# Sonar-Amplifier.net
KiCad netlist of a schematic drawn in EAGLE
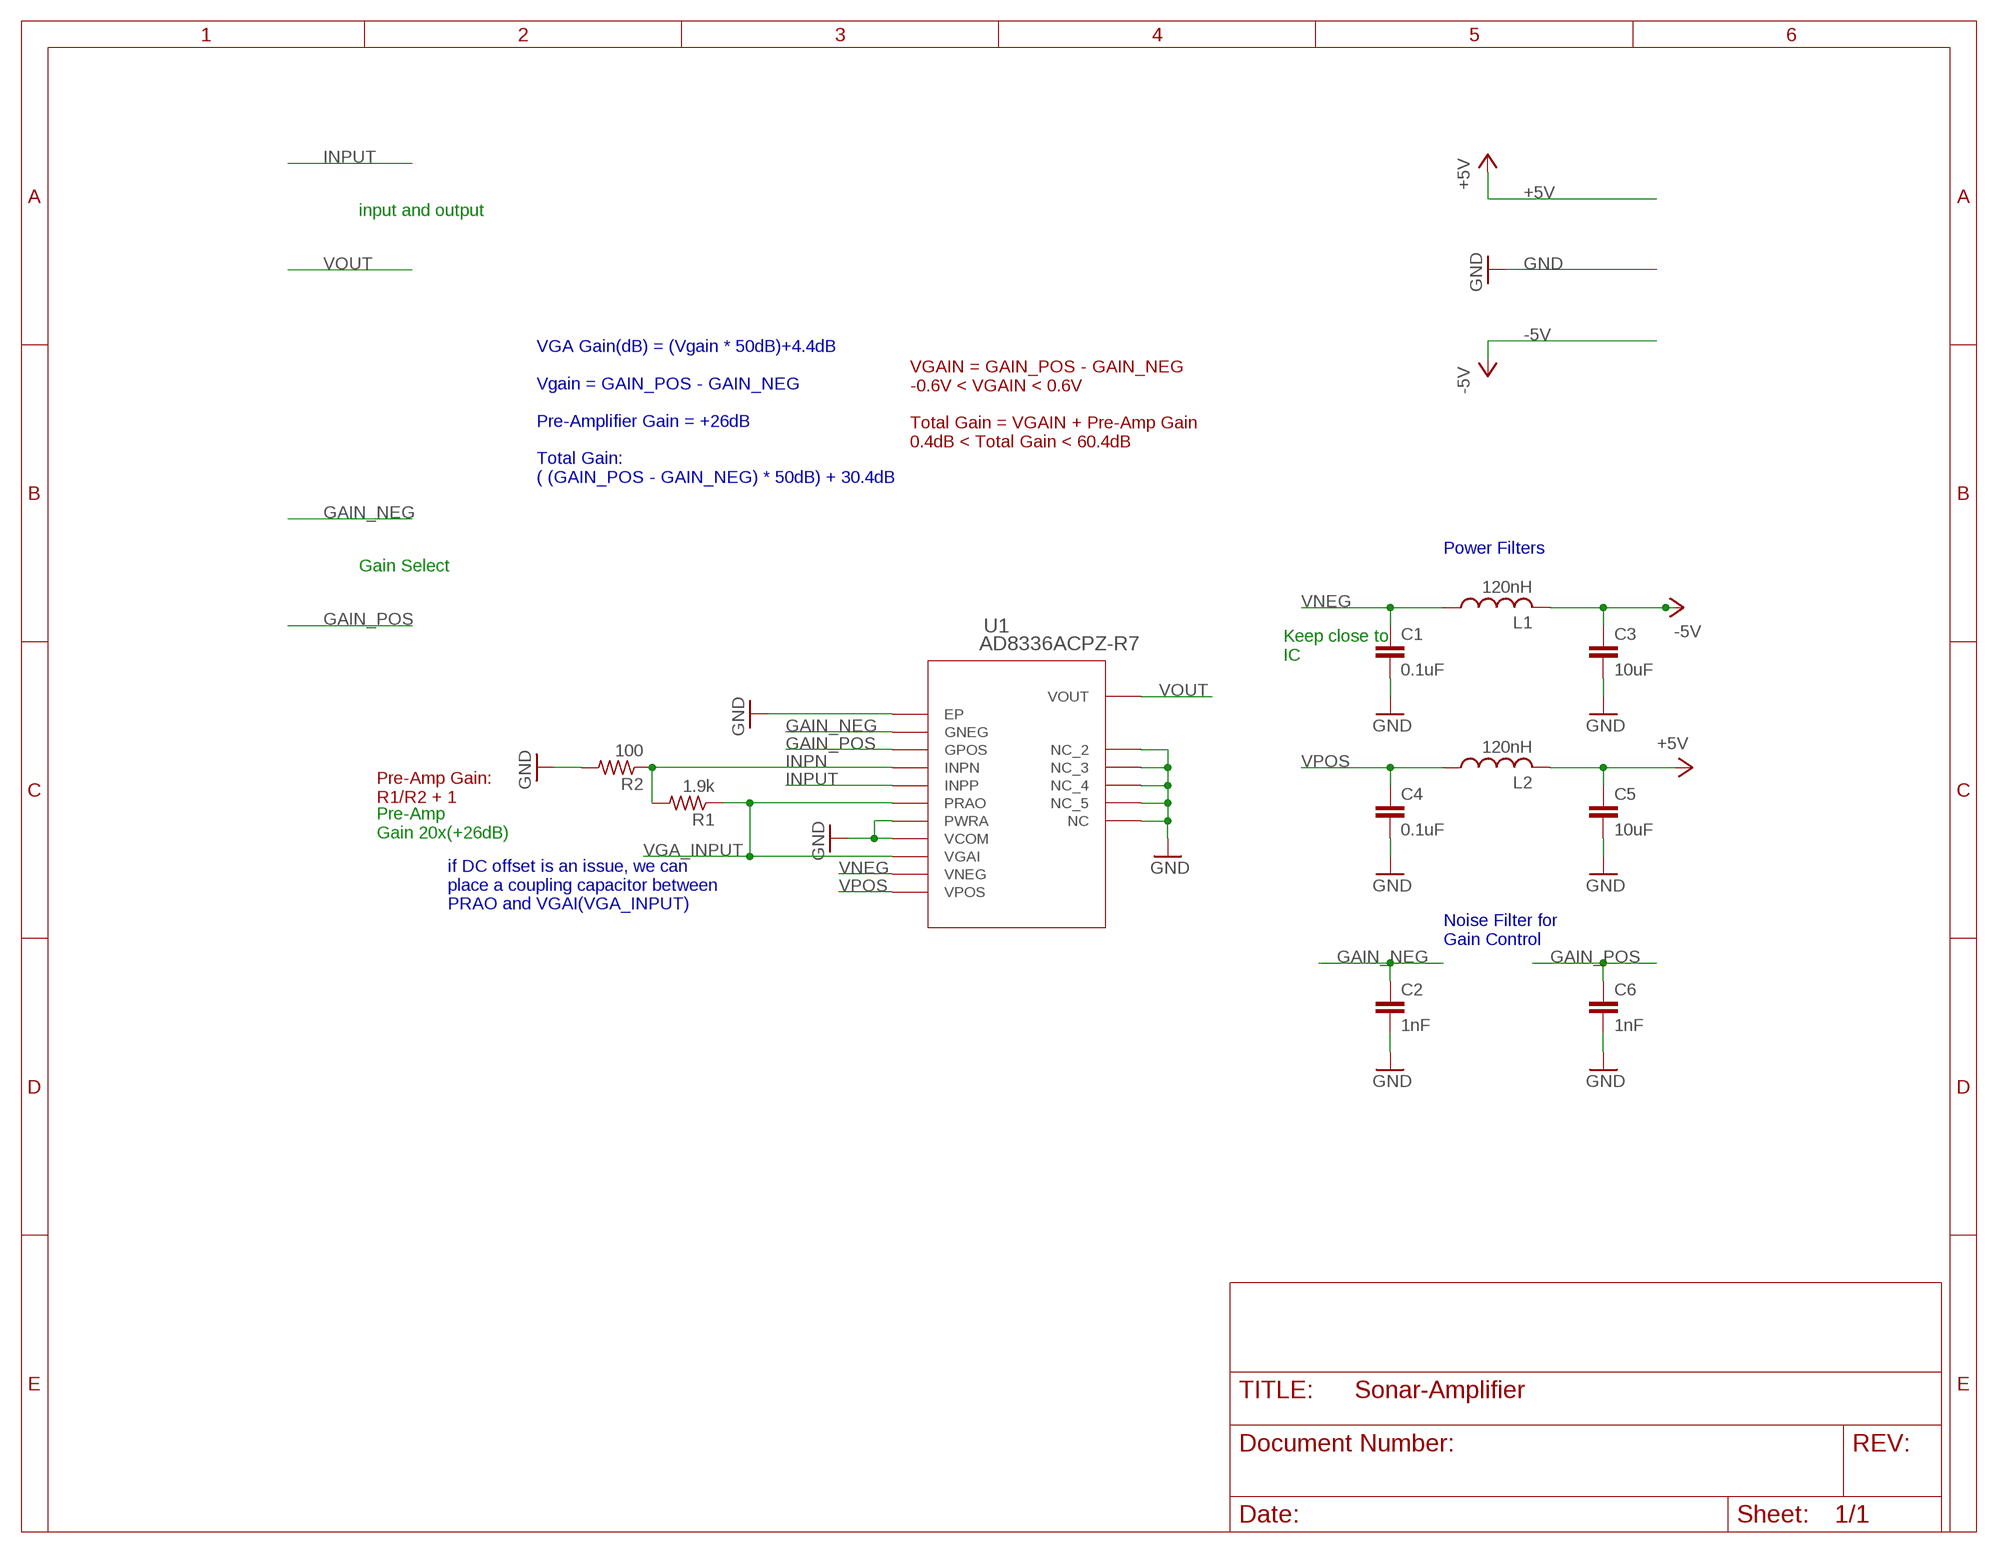
[diagram p0: schematic, sheet 1]

(export (version "E")
  (design (tool "Eeschema 10.0.6"))
  (components
    (comp (ref "C1")
      (value "0.1uF")
      (footprint "eagle-import:C0603")
      (libsource (lib "eagle-import") (part "C-EUC0603"))
    )
    (comp (ref "C2")
      (value "1nF")
      (footprint "eagle-import:C0603")
      (libsource (lib "eagle-import") (part "C-EUC0603"))
    )
    (comp (ref "C3")
      (value "10uF")
      (footprint "eagle-import:C1206")
      (libsource (lib "eagle-import") (part "resistor_348_C-EUC1206"))
    )
    (comp (ref "C4")
      (value "0.1uF")
      (footprint "eagle-import:C0603")
      (libsource (lib "eagle-import") (part "C-EUC0603"))
    )
    (comp (ref "C5")
      (value "10uF")
      (footprint "eagle-import:C1206")
      (libsource (lib "eagle-import") (part "resistor_348_C-EUC1206"))
    )
    (comp (ref "C6")
      (value "1nF")
      (footprint "eagle-import:C0603")
      (libsource (lib "eagle-import") (part "C-EUC0603"))
    )
    (comp (ref "L1")
      (value "120nH")
      (footprint "eagle-import:L3225P")
      (libsource (lib "eagle-import") (part "L-USL3225P"))
    )
    (comp (ref "L2")
      (value "120nH")
      (footprint "eagle-import:L3225P")
      (libsource (lib "eagle-import") (part "L-USL3225P"))
    )
    (comp (ref "R1")
      (value "1.9k")
      (footprint "eagle-import:R0603")
      (libsource (lib "eagle-import") (part "R-US_R0603"))
    )
    (comp (ref "R2")
      (value "100")
      (footprint "eagle-import:R0603")
      (libsource (lib "eagle-import") (part "R-US_R0603"))
    )
    (comp (ref "U1")
      (value "AD8336ACPZ-R7")
      (footprint "eagle-import:CP_16_4")
      (fields (field (name "MANUFACTURER_PART_NUMBER") "AD8336ACPZR7"))
      (libsource (lib "eagle-import") (part "AD8336ACPZ-R7"))
    )
  )
  (nets
    (net (code "1") (name "+5V") (class "Default")
      (node (ref "C5") (pin "1") (pinfunction "1_1") (pintype "passive"))
      (node (ref "L2") (pin "2") (pinfunction "2_2") (pintype "passive"))
    )
    (net (code "2") (name "-5V") (class "Default")
      (node (ref "C3") (pin "1") (pinfunction "1_1") (pintype "passive"))
      (node (ref "L1") (pin "2") (pinfunction "2_2") (pintype "passive"))
    )
    (net (code "3") (name "/GAIN_NEG") (class "Default")
      (node (ref "C2") (pin "1") (pinfunction "1_1") (pintype "passive"))
      (node (ref "U1") (pin "GNEG") (pinfunction "GNEG_GNEG") (pintype "passive"))
    )
    (net (code "4") (name "/GAIN_POS") (class "Default")
      (node (ref "C6") (pin "1") (pinfunction "1_1") (pintype "passive"))
      (node (ref "U1") (pin "GPOS") (pinfunction "GPOS_GPOS") (pintype "passive"))
    )
    (net (code "5") (name "/INPN") (class "Default")
      (node (ref "R1") (pin "2") (pinfunction "2_2") (pintype "passive"))
      (node (ref "R2") (pin "1") (pinfunction "1_1") (pintype "passive"))
      (node (ref "U1") (pin "INPN") (pinfunction "INPN_INPN") (pintype "passive"))
    )
    (net (code "6") (name "/INPUT") (class "Default")
      (node (ref "U1") (pin "INPP") (pinfunction "INPP_INPP") (pintype "passive"))
    )
    (net (code "7") (name "/VGA_INPUT") (class "Default")
      (node (ref "R1") (pin "1") (pinfunction "1_1") (pintype "passive"))
      (node (ref "U1") (pin "PRAO") (pinfunction "PRAO_PRAO") (pintype "passive"))
      (node (ref "U1") (pin "VGAI") (pinfunction "VGAI_VGAI") (pintype "passive"))
    )
    (net (code "8") (name "/VNEG") (class "Default")
      (node (ref "C1") (pin "1") (pinfunction "1_1") (pintype "passive"))
      (node (ref "L1") (pin "1") (pinfunction "1_1") (pintype "passive"))
      (node (ref "U1") (pin "VNEG") (pinfunction "VNEG_VNEG") (pintype "passive"))
    )
    (net (code "9") (name "/VOUT") (class "Default")
      (node (ref "U1") (pin "VOUT") (pinfunction "VOUT_VOUT") (pintype "passive"))
    )
    (net (code "10") (name "/VPOS") (class "Default")
      (node (ref "C4") (pin "1") (pinfunction "1_1") (pintype "passive"))
      (node (ref "L2") (pin "1") (pinfunction "1_1") (pintype "passive"))
      (node (ref "U1") (pin "VPOS") (pinfunction "VPOS_VPOS") (pintype "passive"))
    )
    (net (code "11") (name "GND") (class "Default")
      (node (ref "C1") (pin "2") (pinfunction "2_2") (pintype "passive"))
      (node (ref "C2") (pin "2") (pinfunction "2_2") (pintype "passive"))
      (node (ref "C3") (pin "2") (pinfunction "2_2") (pintype "passive"))
      (node (ref "C4") (pin "2") (pinfunction "2_2") (pintype "passive"))
      (node (ref "C5") (pin "2") (pinfunction "2_2") (pintype "passive"))
      (node (ref "C6") (pin "2") (pinfunction "2_2") (pintype "passive"))
      (node (ref "R2") (pin "2") (pinfunction "2_2") (pintype "passive"))
      (node (ref "U1") (pin "GND1") (pinfunction "EP_GND1") (pintype "passive"))
      (node (ref "U1") (pin "NC") (pinfunction "NC_NC") (pintype "passive"))
      (node (ref "U1") (pin "NC1") (pinfunction "NC_2_NC1") (pintype "passive"))
      (node (ref "U1") (pin "NC2") (pinfunction "NC_3_NC2") (pintype "passive"))
      (node (ref "U1") (pin "NC3") (pinfunction "NC_4_NC3") (pintype "passive"))
      (node (ref "U1") (pin "NC4") (pinfunction "NC_5_NC4") (pintype "passive"))
      (node (ref "U1") (pin "PWRA") (pinfunction "PWRA_PWRA") (pintype "passive"))
      (node (ref "U1") (pin "VCOM") (pinfunction "VCOM_VCOM") (pintype "passive"))
    )
  )
)
